# 09-multimodal-microcontroller-switches-d.net
KiCad netlist of a schematic drawn in Altium Designer
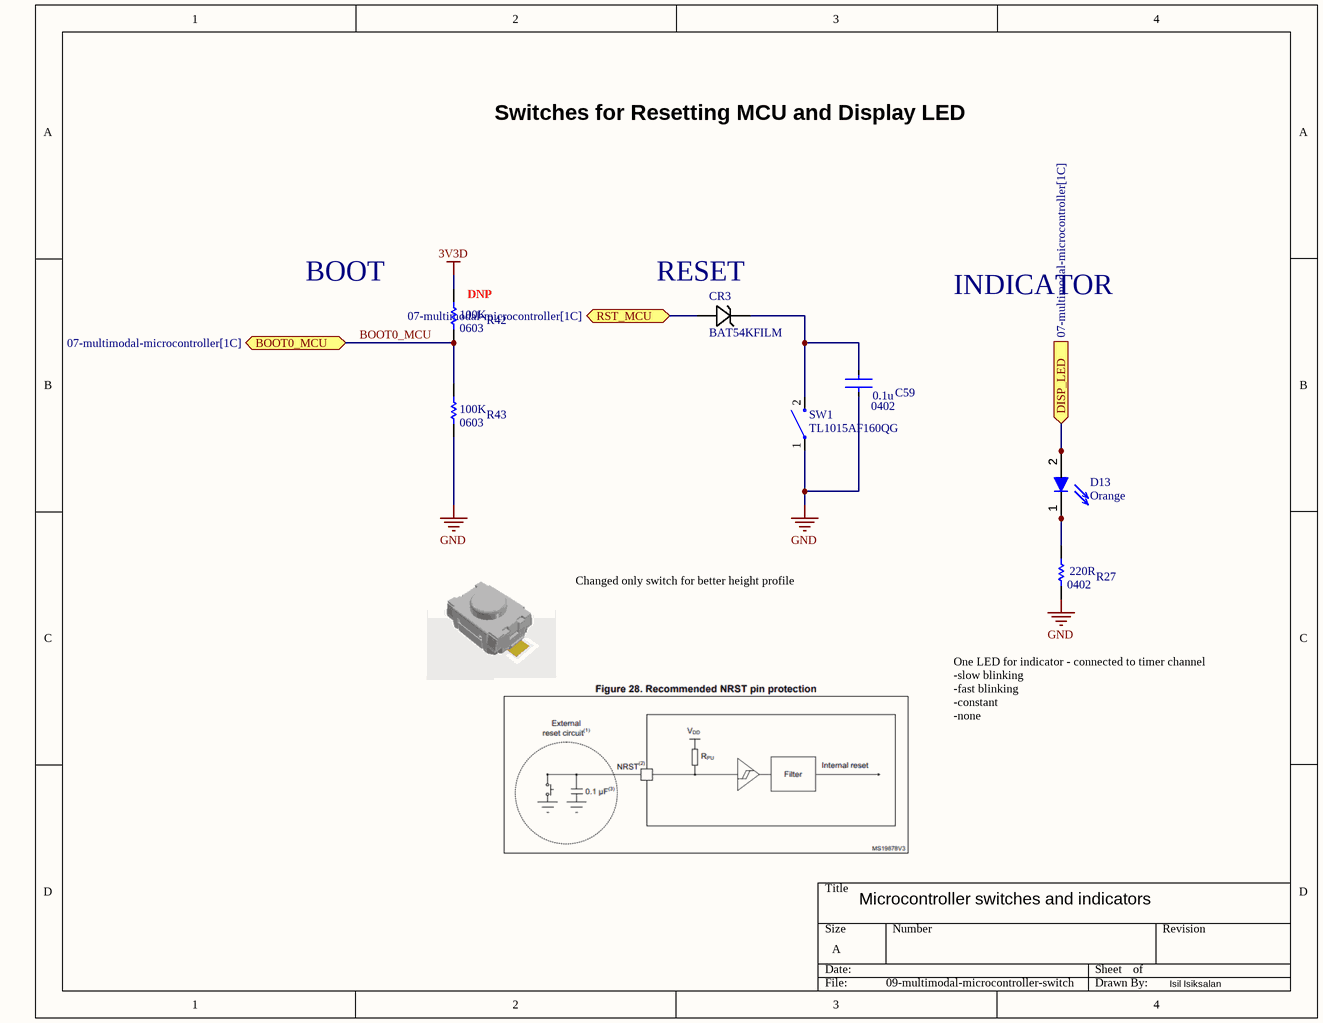
[diagram p0: 09-multimodal-microcontroller-switches-display.SchDoc]

(export (version "E")
  (design (tool "Eeschema 10.0.6"))
  (components
    (comp (ref "C59")
      (value "C1005X7R1H104K050BB")
      (footprint "CAPTDK0402")
      (description "CAP CER 0.1UF 50V X7R 0402")
      (libsource (lib "multimodal") (part "C1005X7R1H104K050BB"))
    )
    (comp (ref "CR3")
      (value "BAT54KFILM")
      (footprint "SOD-523_STM-L")
      (description "40 V, 300 mA General purpose  Signal Schottky Diode")
      (fields (field (name "COPYRIGHT") "Copyright (C) 2025 Ultra Librarian. All rights reserved."))
      (libsource (lib "multimodal") (part "BAT54KFILM"))
    )
    (comp (ref "D13")
      (value "Orange")
      (footprint "DISPLAY-LED")
      (description "LED ORANGE CLEAR 0603 SMD")
      (libsource (lib "multimodal") (part "LTST-C191KFKT"))
    )
    (comp (ref "R27")
      (value "RMCF0402JT220R")
      (footprint "RES-STACK-POLE-0402")
      (description "RES 220 OHM 5% 1/16W 0402")
      (libsource (lib "multimodal") (part "RMCF0402JT220R"))
    )
    (comp (ref "R42")
      (value "RMCF0603JG100K")
      (footprint "RES-STACK-POLE-0603")
      (description "RES 100K OHM 5% 1/10W 0603")
      (libsource (lib "multimodal") (part "RMCF0603JG100K"))
    )
    (comp (ref "R43")
      (value "RMCF0603JG100K")
      (footprint "RES-STACK-POLE-0603")
      (description "RES 100K OHM 5% 1/10W 0603")
      (libsource (lib "multimodal") (part "RMCF0603JG100K"))
    )
    (comp (ref "SW1")
      (value "TL1015AF160QG")
      (footprint "TACTILE-SWITCH")
      (description "SWITCH TACTILE SPST-NO 0.05A 12V")
      (libsource (lib "multimodal") (part "TL1015AF160QG"))
    )
  )
  (nets
    (net (code "1") (name "/BOOT0_MCU") (class "Default")
      (node (ref "R42") (pin "1") (pinfunction "1_1") (pintype "passive"))
      (node (ref "R43") (pin "2") (pinfunction "2_2") (pintype "passive"))
    )
    (net (code "2") (name "/DISP_LED") (class "Default") (node (ref "D13") (pin "2") (pintype "passive")))
    (net (code "3") (name "/RST_MCU") (class "Default")
      (node (ref "CR3") (pin "2") (pinfunction "2_2") (pintype "passive"))
    )
    (net (code "4") (name "3V3D") (class "Default")
      (node (ref "R42") (pin "2") (pinfunction "2_2") (pintype "passive"))
    )
    (net (code "5") (name "GND") (class "Default")
      (node (ref "C59") (pin "2") (pinfunction "2_2") (pintype "passive"))
      (node (ref "R27") (pin "1") (pinfunction "1_1") (pintype "passive"))
      (node (ref "R43") (pin "1") (pinfunction "1_1") (pintype "passive"))
      (node (ref "SW1") (pin "1") (pinfunction "1_1") (pintype "passive"))
    )
    (net (code "6") (name "Net-(C59-Pad1)") (class "Default")
      (node (ref "C59") (pin "1") (pinfunction "1_1") (pintype "passive"))
      (node (ref "CR3") (pin "1") (pinfunction "1_1") (pintype "passive"))
      (node (ref "SW1") (pin "2") (pinfunction "2_2") (pintype "passive"))
    )
    (net (code "7") (name "Net-(D13-Pad1)") (class "Default")
      (node (ref "D13") (pin "1") (pintype "passive"))
      (node (ref "R27") (pin "2") (pinfunction "2_2") (pintype "passive"))
    )
  )
)
